# Interconnect_board_v1p7.net
KiCad netlist of a schematic drawn in EAGLE
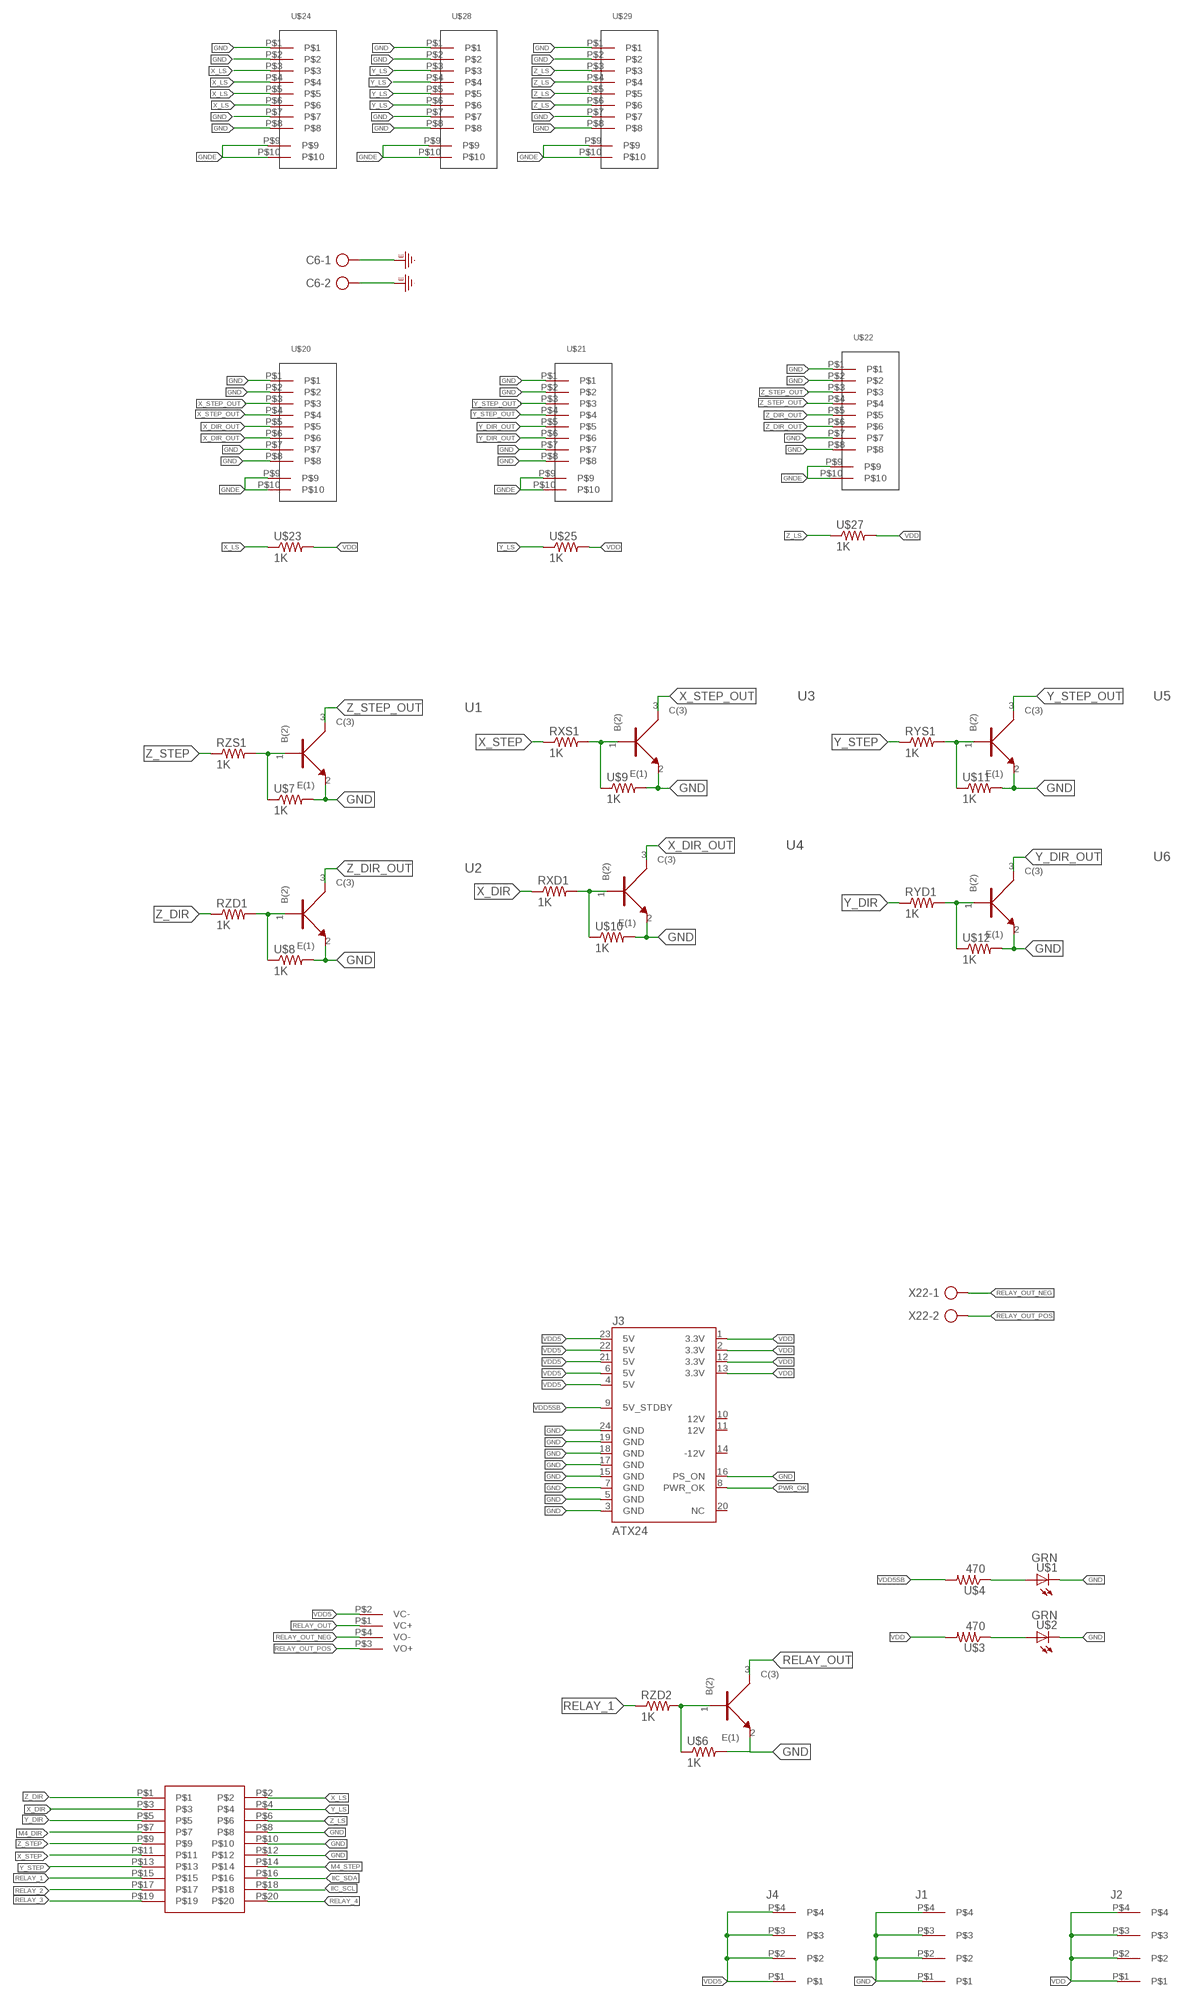
[diagram p0: schematic, sheet 1]

(export (version "E")
  (design (tool "Eeschema 10.0.6"))
  (components
    (comp (ref "C6")
      (value "AK300/2")
      (footprint "eagle-import:AK300_2")
      (libsource (lib "eagle-import") (part "AK300/2"))
    )
    (comp (ref "J1")
      (value "3.81MM_1_X_4_RT_ANGLE_PLUG_HEADER")
      (footprint "eagle-import:1X4_3.81MM_PITCH")
      (libsource (lib "eagle-import") (part "3.81MM_1_X_4_RT_ANGLE_PLUG_HEADER"))
    )
    (comp (ref "J2")
      (value "3.81MM_1_X_4_RT_ANGLE_PLUG_HEADER")
      (footprint "eagle-import:1X4_3.81MM_PITCH")
      (libsource (lib "eagle-import") (part "3.81MM_1_X_4_RT_ANGLE_PLUG_HEADER"))
    )
    (comp (ref "J3")
      (value "ATX24")
      (footprint "eagle-import:ATX24_STRAIGHT")
      (libsource (lib "eagle-import") (part "ATX24"))
    )
    (comp (ref "J4")
      (value "3.81MM_1_X_4_RT_ANGLE_PLUG_HEADER")
      (footprint "eagle-import:1X4_3.81MM_PITCH")
      (libsource (lib "eagle-import") (part "3.81MM_1_X_4_RT_ANGLE_PLUG_HEADER"))
    )
    (comp (ref "RXD1")
      (value "R_0805_1K")
      (footprint "eagle-import:R_0805_1K")
      (libsource (lib "eagle-import") (part "R_0805_1K"))
    )
    (comp (ref "RXS1")
      (value "R_0805_1K")
      (footprint "eagle-import:R_0805_1K")
      (libsource (lib "eagle-import") (part "R_0805_1K"))
    )
    (comp (ref "RYD1")
      (value "R_0805_1K")
      (footprint "eagle-import:R_0805_1K")
      (libsource (lib "eagle-import") (part "R_0805_1K"))
    )
    (comp (ref "RYS1")
      (value "R_0805_1K")
      (footprint "eagle-import:R_0805_1K")
      (libsource (lib "eagle-import") (part "R_0805_1K"))
    )
    (comp (ref "RZD1")
      (value "R_0805_1K")
      (footprint "eagle-import:R_0805_1K")
      (libsource (lib "eagle-import") (part "R_0805_1K"))
    )
    (comp (ref "RZD2")
      (value "R_0805_1K")
      (footprint "eagle-import:R_0805_1K")
      (libsource (lib "eagle-import") (part "R_0805_1K"))
    )
    (comp (ref "RZS1")
      (value "R_0805_1K")
      (footprint "eagle-import:R_0805_1K")
      (libsource (lib "eagle-import") (part "R_0805_1K"))
    )
    (comp (ref "U$1")
      (value "LED_0805_GREEN")
      (footprint "eagle-import:LED_0805_GREEN")
      (libsource (lib "eagle-import") (part "LED_0805_GREEN"))
    )
    (comp (ref "U$2")
      (value "LED_0805_GREEN")
      (footprint "eagle-import:LED_0805_GREEN")
      (libsource (lib "eagle-import") (part "LED_0805_GREEN"))
    )
    (comp (ref "U$3")
      (value "R_0805_470")
      (footprint "eagle-import:R_0805_470")
      (libsource (lib "eagle-import") (part "R_0805_470"))
    )
    (comp (ref "U$4")
      (value "R_0805_470")
      (footprint "eagle-import:R_0805_470")
      (libsource (lib "eagle-import") (part "R_0805_470"))
    )
    (comp (ref "U$5")
      (value "RELAY_KYOTO_KF0604D")
      (footprint "eagle-import:RELAY_KYOTO_KF0604D")
      (libsource (lib "eagle-import") (part "RELAY_KYOTO_KF0604D"))
    )
    (comp (ref "U$6")
      (value "R_0805_1K")
      (footprint "eagle-import:R_0805_1K")
      (libsource (lib "eagle-import") (part "R_0805_1K"))
    )
    (comp (ref "U$7")
      (value "R_0805_1K")
      (footprint "eagle-import:R_0805_1K")
      (libsource (lib "eagle-import") (part "R_0805_1K"))
    )
    (comp (ref "U$8")
      (value "R_0805_1K")
      (footprint "eagle-import:R_0805_1K")
      (libsource (lib "eagle-import") (part "R_0805_1K"))
    )
    (comp (ref "U$9")
      (value "R_0805_1K")
      (footprint "eagle-import:R_0805_1K")
      (libsource (lib "eagle-import") (part "R_0805_1K"))
    )
    (comp (ref "U$10")
      (value "R_0805_1K")
      (footprint "eagle-import:R_0805_1K")
      (libsource (lib "eagle-import") (part "R_0805_1K"))
    )
    (comp (ref "U$11")
      (value "R_0805_1K")
      (footprint "eagle-import:R_0805_1K")
      (libsource (lib "eagle-import") (part "R_0805_1K"))
    )
    (comp (ref "U$12")
      (value "R_0805_1K")
      (footprint "eagle-import:R_0805_1K")
      (libsource (lib "eagle-import") (part "R_0805_1K"))
    )
    (comp (ref "U$20")
      (value "RJ45_SMTRJ")
      (footprint "eagle-import:RJ45_SMT")
      (libsource (lib "eagle-import") (part "RJ45_SMTRJ"))
    )
    (comp (ref "U$21")
      (value "RJ45_SMTRJ")
      (footprint "eagle-import:RJ45_SMT")
      (libsource (lib "eagle-import") (part "RJ45_SMTRJ"))
    )
    (comp (ref "U$22")
      (value "RJ45_SMTRJ")
      (footprint "eagle-import:RJ45_SMT")
      (libsource (lib "eagle-import") (part "RJ45_SMTRJ"))
    )
    (comp (ref "U$23")
      (value "R_0805_1K")
      (footprint "eagle-import:R_0805_1K")
      (libsource (lib "eagle-import") (part "R_0805_1K"))
    )
    (comp (ref "U$24")
      (value "RJ45_SMTRJ")
      (footprint "eagle-import:RJ45_SMT")
      (libsource (lib "eagle-import") (part "RJ45_SMTRJ"))
    )
    (comp (ref "U$25")
      (value "R_0805_1K")
      (footprint "eagle-import:R_0805_1K")
      (libsource (lib "eagle-import") (part "R_0805_1K"))
    )
    (comp (ref "U$26")
      (value "2_X_10_HEADER_GENERIC")
      (footprint "eagle-import:2_X_10_.1_INCH")
      (libsource (lib "eagle-import") (part "2_X_10_HEADER_GENERIC"))
    )
    (comp (ref "U$27")
      (value "R_0805_1K")
      (footprint "eagle-import:R_0805_1K")
      (libsource (lib "eagle-import") (part "R_0805_1K"))
    )
    (comp (ref "U$28")
      (value "RJ45_SMTRJ")
      (footprint "eagle-import:RJ45_SMT")
      (libsource (lib "eagle-import") (part "RJ45_SMTRJ"))
    )
    (comp (ref "U$29")
      (value "RJ45_SMTRJ")
      (footprint "eagle-import:RJ45_SMT")
      (libsource (lib "eagle-import") (part "RJ45_SMTRJ"))
    )
    (comp (ref "U1")
      (value "BC846BW")
      (footprint "eagle-import:SOT323")
      (libsource (lib "eagle-import") (part "BC846BW"))
    )
    (comp (ref "U2")
      (value "BC846BW")
      (footprint "eagle-import:SOT323")
      (libsource (lib "eagle-import") (part "BC846BW"))
    )
    (comp (ref "U3")
      (value "BC846BW")
      (footprint "eagle-import:SOT323")
      (libsource (lib "eagle-import") (part "BC846BW"))
    )
    (comp (ref "U4")
      (value "BC846BW")
      (footprint "eagle-import:SOT323")
      (libsource (lib "eagle-import") (part "BC846BW"))
    )
    (comp (ref "U5")
      (value "BC846BW")
      (footprint "eagle-import:SOT323")
      (libsource (lib "eagle-import") (part "BC846BW"))
    )
    (comp (ref "U6")
      (value "BC846BW")
      (footprint "eagle-import:SOT323")
      (libsource (lib "eagle-import") (part "BC846BW"))
    )
    (comp (ref "U7")
      (value "BC846BW")
      (footprint "eagle-import:SOT323")
      (libsource (lib "eagle-import") (part "BC846BW"))
    )
    (comp (ref "X22")
      (value "AK300/2")
      (footprint "eagle-import:AK300_2")
      (libsource (lib "eagle-import") (part "AK300/2"))
    )
  )
  (nets
    (net (code "1") (name "GND") (class "Default")
      (node (ref "J1") (pin "P$1") (pinfunction "P$1_P$1") (pintype "bidirectional"))
      (node (ref "J1") (pin "P$2") (pinfunction "P$2_P$2") (pintype "bidirectional"))
      (node (ref "J1") (pin "P$3") (pinfunction "P$3_P$3") (pintype "bidirectional"))
      (node (ref "J1") (pin "P$4") (pinfunction "P$4_P$4") (pintype "bidirectional"))
      (node (ref "J3") (pin "15") (pinfunction "GND_15") (pintype "bidirectional"))
      (node (ref "J3") (pin "16") (pinfunction "PS_ON_16") (pintype "bidirectional"))
      (node (ref "J3") (pin "17") (pinfunction "GND_17") (pintype "bidirectional"))
      (node (ref "J3") (pin "18") (pinfunction "GND_18") (pintype "bidirectional"))
      (node (ref "J3") (pin "19") (pinfunction "GND_19") (pintype "bidirectional"))
      (node (ref "J3") (pin "24") (pinfunction "GND_24") (pintype "bidirectional"))
      (node (ref "J3") (pin "3") (pinfunction "GND_3") (pintype "bidirectional"))
      (node (ref "J3") (pin "5") (pinfunction "GND_5") (pintype "bidirectional"))
      (node (ref "J3") (pin "7") (pinfunction "GND_7") (pintype "bidirectional"))
      (node (ref "U$1") (pin "C") (pinfunction "C_C") (pintype "passive"))
      (node (ref "U$10") (pin "2") (pinfunction "2_2") (pintype "passive"))
      (node (ref "U$11") (pin "2") (pinfunction "2_2") (pintype "passive"))
      (node (ref "U$12") (pin "2") (pinfunction "2_2") (pintype "passive"))
      (node (ref "U$2") (pin "C") (pinfunction "C_C") (pintype "passive"))
      (node (ref "U$20") (pin "P$1") (pinfunction "P$1_P$1") (pintype "bidirectional"))
      (node (ref "U$20") (pin "P$2") (pinfunction "P$2_P$2") (pintype "bidirectional"))
      (node (ref "U$20") (pin "P$7") (pinfunction "P$7_P$7") (pintype "bidirectional"))
      (node (ref "U$20") (pin "P$8") (pinfunction "P$8_P$8") (pintype "bidirectional"))
      (node (ref "U$21") (pin "P$1") (pinfunction "P$1_P$1") (pintype "bidirectional"))
      (node (ref "U$21") (pin "P$2") (pinfunction "P$2_P$2") (pintype "bidirectional"))
      (node (ref "U$21") (pin "P$7") (pinfunction "P$7_P$7") (pintype "bidirectional"))
      (node (ref "U$21") (pin "P$8") (pinfunction "P$8_P$8") (pintype "bidirectional"))
      (node (ref "U$22") (pin "P$1") (pinfunction "P$1_P$1") (pintype "bidirectional"))
      (node (ref "U$22") (pin "P$2") (pinfunction "P$2_P$2") (pintype "bidirectional"))
      (node (ref "U$22") (pin "P$7") (pinfunction "P$7_P$7") (pintype "bidirectional"))
      (node (ref "U$22") (pin "P$8") (pinfunction "P$8_P$8") (pintype "bidirectional"))
      (node (ref "U$24") (pin "P$1") (pinfunction "P$1_P$1") (pintype "bidirectional"))
      (node (ref "U$24") (pin "P$2") (pinfunction "P$2_P$2") (pintype "bidirectional"))
      (node (ref "U$24") (pin "P$7") (pinfunction "P$7_P$7") (pintype "bidirectional"))
      (node (ref "U$24") (pin "P$8") (pinfunction "P$8_P$8") (pintype "bidirectional"))
      (node (ref "U$26") (pin "P$10") (pinfunction "P$10_P$10") (pintype "bidirectional"))
      (node (ref "U$26") (pin "P$12") (pinfunction "P$12_P$12") (pintype "bidirectional"))
      (node (ref "U$26") (pin "P$8") (pinfunction "P$8_P$8") (pintype "bidirectional"))
      (node (ref "U$28") (pin "P$1") (pinfunction "P$1_P$1") (pintype "bidirectional"))
      (node (ref "U$28") (pin "P$2") (pinfunction "P$2_P$2") (pintype "bidirectional"))
      (node (ref "U$28") (pin "P$7") (pinfunction "P$7_P$7") (pintype "bidirectional"))
      (node (ref "U$28") (pin "P$8") (pinfunction "P$8_P$8") (pintype "bidirectional"))
      (node (ref "U$29") (pin "P$1") (pinfunction "P$1_P$1") (pintype "bidirectional"))
      (node (ref "U$29") (pin "P$2") (pinfunction "P$2_P$2") (pintype "bidirectional"))
      (node (ref "U$29") (pin "P$7") (pinfunction "P$7_P$7") (pintype "bidirectional"))
      (node (ref "U$29") (pin "P$8") (pinfunction "P$8_P$8") (pintype "bidirectional"))
      (node (ref "U$6") (pin "2") (pinfunction "2_2") (pintype "passive"))
      (node (ref "U$7") (pin "2") (pinfunction "2_2") (pintype "passive"))
      (node (ref "U$8") (pin "2") (pinfunction "2_2") (pintype "passive"))
      (node (ref "U$9") (pin "2") (pinfunction "2_2") (pintype "passive"))
      (node (ref "U1") (pin "2") (pinfunction "E(1)_2") (pintype "output"))
      (node (ref "U2") (pin "2") (pinfunction "E(1)_2") (pintype "output"))
      (node (ref "U3") (pin "2") (pinfunction "E(1)_2") (pintype "output"))
      (node (ref "U4") (pin "2") (pinfunction "E(1)_2") (pintype "output"))
      (node (ref "U5") (pin "2") (pinfunction "E(1)_2") (pintype "output"))
      (node (ref "U6") (pin "2") (pinfunction "E(1)_2") (pintype "output"))
      (node (ref "U7") (pin "2") (pinfunction "E(1)_2") (pintype "output"))
    )
    (net (code "2") (name "GNDE") (class "Default")
      (node (ref "C6") (pin "1") (pinfunction "KL_1") (pintype "passive"))
      (node (ref "C6") (pin "2") (pinfunction "KL_2") (pintype "passive"))
      (node (ref "U$20") (pin "P$10") (pinfunction "P$10_P$10") (pintype "bidirectional"))
      (node (ref "U$20") (pin "P$9") (pinfunction "P$9_P$9") (pintype "bidirectional"))
      (node (ref "U$21") (pin "P$10") (pinfunction "P$10_P$10") (pintype "bidirectional"))
      (node (ref "U$21") (pin "P$9") (pinfunction "P$9_P$9") (pintype "bidirectional"))
      (node (ref "U$22") (pin "P$10") (pinfunction "P$10_P$10") (pintype "bidirectional"))
      (node (ref "U$22") (pin "P$9") (pinfunction "P$9_P$9") (pintype "bidirectional"))
      (node (ref "U$24") (pin "P$10") (pinfunction "P$10_P$10") (pintype "bidirectional"))
      (node (ref "U$24") (pin "P$9") (pinfunction "P$9_P$9") (pintype "bidirectional"))
      (node (ref "U$28") (pin "P$10") (pinfunction "P$10_P$10") (pintype "bidirectional"))
      (node (ref "U$28") (pin "P$9") (pinfunction "P$9_P$9") (pintype "bidirectional"))
      (node (ref "U$29") (pin "P$10") (pinfunction "P$10_P$10") (pintype "bidirectional"))
      (node (ref "U$29") (pin "P$9") (pinfunction "P$9_P$9") (pintype "bidirectional"))
    )
    (net (code "3") (name "IIC_SCL") (class "Default")
      (node (ref "U$26") (pin "P$18") (pinfunction "P$18_P$18") (pintype "bidirectional"))
    )
    (net (code "4") (name "IIC_SDA") (class "Default")
      (node (ref "U$26") (pin "P$16") (pinfunction "P$16_P$16") (pintype "bidirectional"))
    )
    (net (code "5") (name "M4_DIR") (class "Default")
      (node (ref "U$26") (pin "P$7") (pinfunction "P$7_P$7") (pintype "bidirectional"))
    )
    (net (code "6") (name "M4_STEP") (class "Default")
      (node (ref "U$26") (pin "P$14") (pinfunction "P$14_P$14") (pintype "bidirectional"))
    )
    (net (code "7") (name "Net-(U$1-PadA)") (class "Default")
      (node (ref "U$1") (pin "A") (pinfunction "A_A") (pintype "passive"))
      (node (ref "U$4") (pin "1") (pinfunction "1_1") (pintype "passive"))
    )
    (net (code "8") (name "Net-(U$2-PadA)") (class "Default")
      (node (ref "U$2") (pin "A") (pinfunction "A_A") (pintype "passive"))
      (node (ref "U$3") (pin "1") (pinfunction "1_1") (pintype "passive"))
    )
    (net (code "9") (name "Net-(U1-B(2))") (class "Default")
      (node (ref "RZS1") (pin "2") (pinfunction "2_2") (pintype "passive"))
      (node (ref "U$7") (pin "1") (pinfunction "1_1") (pintype "passive"))
      (node (ref "U1") (pin "1") (pinfunction "B(2)_1") (pintype "input"))
    )
    (net (code "10") (name "Net-(U2-B(2))") (class "Default")
      (node (ref "RZD1") (pin "2") (pinfunction "2_2") (pintype "passive"))
      (node (ref "U$8") (pin "1") (pinfunction "1_1") (pintype "passive"))
      (node (ref "U2") (pin "1") (pinfunction "B(2)_1") (pintype "input"))
    )
    (net (code "11") (name "Net-(U3-B(2))") (class "Default")
      (node (ref "RXS1") (pin "2") (pinfunction "2_2") (pintype "passive"))
      (node (ref "U$9") (pin "1") (pinfunction "1_1") (pintype "passive"))
      (node (ref "U3") (pin "1") (pinfunction "B(2)_1") (pintype "input"))
    )
    (net (code "12") (name "Net-(U4-B(2))") (class "Default")
      (node (ref "RXD1") (pin "2") (pinfunction "2_2") (pintype "passive"))
      (node (ref "U$10") (pin "1") (pinfunction "1_1") (pintype "passive"))
      (node (ref "U4") (pin "1") (pinfunction "B(2)_1") (pintype "input"))
    )
    (net (code "13") (name "Net-(U5-B(2))") (class "Default")
      (node (ref "RYS1") (pin "2") (pinfunction "2_2") (pintype "passive"))
      (node (ref "U$11") (pin "1") (pinfunction "1_1") (pintype "passive"))
      (node (ref "U5") (pin "1") (pinfunction "B(2)_1") (pintype "input"))
    )
    (net (code "14") (name "Net-(U6-B(2))") (class "Default")
      (node (ref "RYD1") (pin "2") (pinfunction "2_2") (pintype "passive"))
      (node (ref "U$12") (pin "1") (pinfunction "1_1") (pintype "passive"))
      (node (ref "U6") (pin "1") (pinfunction "B(2)_1") (pintype "input"))
    )
    (net (code "15") (name "Net-(U7-B(2))") (class "Default")
      (node (ref "RZD2") (pin "2") (pinfunction "2_2") (pintype "passive"))
      (node (ref "U$6") (pin "1") (pinfunction "1_1") (pintype "passive"))
      (node (ref "U7") (pin "1") (pinfunction "B(2)_1") (pintype "input"))
    )
    (net (code "16") (name "PWR_OK") (class "Default")
      (node (ref "J3") (pin "8") (pinfunction "PWR_OK_8") (pintype "bidirectional"))
    )
    (net (code "17") (name "RELAY_1") (class "Default")
      (node (ref "RZD2") (pin "1") (pinfunction "1_1") (pintype "passive"))
      (node (ref "U$26") (pin "P$15") (pinfunction "P$15_P$15") (pintype "bidirectional"))
    )
    (net (code "18") (name "RELAY_2") (class "Default")
      (node (ref "U$26") (pin "P$17") (pinfunction "P$17_P$17") (pintype "bidirectional"))
    )
    (net (code "19") (name "RELAY_3") (class "Default")
      (node (ref "U$26") (pin "P$19") (pinfunction "P$19_P$19") (pintype "bidirectional"))
    )
    (net (code "20") (name "RELAY_4") (class "Default")
      (node (ref "U$26") (pin "P$20") (pinfunction "P$20_P$20") (pintype "bidirectional"))
    )
    (net (code "21") (name "RELAY_OUT") (class "Default")
      (node (ref "U$5") (pin "P$1") (pinfunction "VC+_P$1") (pintype "bidirectional"))
      (node (ref "U7") (pin "3") (pinfunction "C(3)_3") (pintype "input"))
    )
    (net (code "22") (name "RELAY_OUT_NEG") (class "Default")
      (node (ref "U$5") (pin "P$4") (pinfunction "VO-_P$4") (pintype "bidirectional"))
      (node (ref "X22") (pin "1") (pinfunction "KL_1") (pintype "passive"))
    )
    (net (code "23") (name "RELAY_OUT_POS") (class "Default")
      (node (ref "U$5") (pin "P$3") (pinfunction "VO+_P$3") (pintype "bidirectional"))
      (node (ref "X22") (pin "2") (pinfunction "KL_2") (pintype "passive"))
    )
    (net (code "24") (name "VDD") (class "Default")
      (node (ref "J2") (pin "P$1") (pinfunction "P$1_P$1") (pintype "bidirectional"))
      (node (ref "J2") (pin "P$2") (pinfunction "P$2_P$2") (pintype "bidirectional"))
      (node (ref "J2") (pin "P$3") (pinfunction "P$3_P$3") (pintype "bidirectional"))
      (node (ref "J2") (pin "P$4") (pinfunction "P$4_P$4") (pintype "bidirectional"))
      (node (ref "J3") (pin "1") (pinfunction "3.3V_1") (pintype "bidirectional"))
      (node (ref "J3") (pin "12") (pinfunction "3.3V_12") (pintype "bidirectional"))
      (node (ref "J3") (pin "13") (pinfunction "3.3V_13") (pintype "bidirectional"))
      (node (ref "J3") (pin "2") (pinfunction "3.3V_2") (pintype "bidirectional"))
      (node (ref "U$23") (pin "2") (pinfunction "2_2") (pintype "passive"))
      (node (ref "U$25") (pin "2") (pinfunction "2_2") (pintype "passive"))
      (node (ref "U$27") (pin "2") (pinfunction "2_2") (pintype "passive"))
      (node (ref "U$3") (pin "2") (pinfunction "2_2") (pintype "passive"))
    )
    (net (code "25") (name "VDD5") (class "Default")
      (node (ref "J3") (pin "21") (pinfunction "5V_21") (pintype "bidirectional"))
      (node (ref "J3") (pin "22") (pinfunction "5V_22") (pintype "bidirectional"))
      (node (ref "J3") (pin "23") (pinfunction "5V_23") (pintype "bidirectional"))
      (node (ref "J3") (pin "4") (pinfunction "5V_4") (pintype "bidirectional"))
      (node (ref "J3") (pin "6") (pinfunction "5V_6") (pintype "bidirectional"))
      (node (ref "J4") (pin "P$1") (pinfunction "P$1_P$1") (pintype "bidirectional"))
      (node (ref "J4") (pin "P$2") (pinfunction "P$2_P$2") (pintype "bidirectional"))
      (node (ref "J4") (pin "P$3") (pinfunction "P$3_P$3") (pintype "bidirectional"))
      (node (ref "J4") (pin "P$4") (pinfunction "P$4_P$4") (pintype "bidirectional"))
      (node (ref "U$5") (pin "P$2") (pinfunction "VC-_P$2") (pintype "bidirectional"))
    )
    (net (code "26") (name "VDD5SB") (class "Default")
      (node (ref "J3") (pin "9") (pinfunction "5V_STDBY_9") (pintype "bidirectional"))
      (node (ref "U$4") (pin "2") (pinfunction "2_2") (pintype "passive"))
    )
    (net (code "27") (name "X_DIR") (class "Default")
      (node (ref "RXD1") (pin "1") (pinfunction "1_1") (pintype "passive"))
      (node (ref "U$26") (pin "P$3") (pinfunction "P$3_P$3") (pintype "bidirectional"))
    )
    (net (code "28") (name "X_DIR_OUT") (class "Default")
      (node (ref "U$20") (pin "P$5") (pinfunction "P$5_P$5") (pintype "bidirectional"))
      (node (ref "U$20") (pin "P$6") (pinfunction "P$6_P$6") (pintype "bidirectional"))
      (node (ref "U4") (pin "3") (pinfunction "C(3)_3") (pintype "input"))
    )
    (net (code "29") (name "X_LS") (class "Default")
      (node (ref "U$23") (pin "1") (pinfunction "1_1") (pintype "passive"))
      (node (ref "U$24") (pin "P$3") (pinfunction "P$3_P$3") (pintype "bidirectional"))
      (node (ref "U$24") (pin "P$4") (pinfunction "P$4_P$4") (pintype "bidirectional"))
      (node (ref "U$24") (pin "P$5") (pinfunction "P$5_P$5") (pintype "bidirectional"))
      (node (ref "U$24") (pin "P$6") (pinfunction "P$6_P$6") (pintype "bidirectional"))
      (node (ref "U$26") (pin "P$2") (pinfunction "P$2_P$2") (pintype "bidirectional"))
    )
    (net (code "30") (name "X_STEP") (class "Default")
      (node (ref "RXS1") (pin "1") (pinfunction "1_1") (pintype "passive"))
      (node (ref "U$26") (pin "P$11") (pinfunction "P$11_P$11") (pintype "bidirectional"))
    )
    (net (code "31") (name "X_STEP_OUT") (class "Default")
      (node (ref "U$20") (pin "P$3") (pinfunction "P$3_P$3") (pintype "bidirectional"))
      (node (ref "U$20") (pin "P$4") (pinfunction "P$4_P$4") (pintype "bidirectional"))
      (node (ref "U3") (pin "3") (pinfunction "C(3)_3") (pintype "input"))
    )
    (net (code "32") (name "Y_DIR") (class "Default")
      (node (ref "RYD1") (pin "1") (pinfunction "1_1") (pintype "passive"))
      (node (ref "U$26") (pin "P$5") (pinfunction "P$5_P$5") (pintype "bidirectional"))
    )
    (net (code "33") (name "Y_DIR_OUT") (class "Default")
      (node (ref "U$21") (pin "P$5") (pinfunction "P$5_P$5") (pintype "bidirectional"))
      (node (ref "U$21") (pin "P$6") (pinfunction "P$6_P$6") (pintype "bidirectional"))
      (node (ref "U6") (pin "3") (pinfunction "C(3)_3") (pintype "input"))
    )
    (net (code "34") (name "Y_LS") (class "Default")
      (node (ref "U$25") (pin "1") (pinfunction "1_1") (pintype "passive"))
      (node (ref "U$26") (pin "P$4") (pinfunction "P$4_P$4") (pintype "bidirectional"))
      (node (ref "U$28") (pin "P$3") (pinfunction "P$3_P$3") (pintype "bidirectional"))
      (node (ref "U$28") (pin "P$4") (pinfunction "P$4_P$4") (pintype "bidirectional"))
      (node (ref "U$28") (pin "P$5") (pinfunction "P$5_P$5") (pintype "bidirectional"))
      (node (ref "U$28") (pin "P$6") (pinfunction "P$6_P$6") (pintype "bidirectional"))
    )
    (net (code "35") (name "Y_STEP") (class "Default")
      (node (ref "RYS1") (pin "1") (pinfunction "1_1") (pintype "passive"))
      (node (ref "U$26") (pin "P$13") (pinfunction "P$13_P$13") (pintype "bidirectional"))
    )
    (net (code "36") (name "Y_STEP_OUT") (class "Default")
      (node (ref "U$21") (pin "P$3") (pinfunction "P$3_P$3") (pintype "bidirectional"))
      (node (ref "U$21") (pin "P$4") (pinfunction "P$4_P$4") (pintype "bidirectional"))
      (node (ref "U5") (pin "3") (pinfunction "C(3)_3") (pintype "input"))
    )
    (net (code "37") (name "Z_DIR") (class "Default")
      (node (ref "RZD1") (pin "1") (pinfunction "1_1") (pintype "passive"))
      (node (ref "U$26") (pin "P$1") (pinfunction "P$1_P$1") (pintype "bidirectional"))
    )
    (net (code "38") (name "Z_DIR_OUT") (class "Default")
      (node (ref "U$22") (pin "P$5") (pinfunction "P$5_P$5") (pintype "bidirectional"))
      (node (ref "U$22") (pin "P$6") (pinfunction "P$6_P$6") (pintype "bidirectional"))
      (node (ref "U2") (pin "3") (pinfunction "C(3)_3") (pintype "input"))
    )
    (net (code "39") (name "Z_LS") (class "Default")
      (node (ref "U$26") (pin "P$6") (pinfunction "P$6_P$6") (pintype "bidirectional"))
      (node (ref "U$27") (pin "1") (pinfunction "1_1") (pintype "passive"))
      (node (ref "U$29") (pin "P$3") (pinfunction "P$3_P$3") (pintype "bidirectional"))
      (node (ref "U$29") (pin "P$4") (pinfunction "P$4_P$4") (pintype "bidirectional"))
      (node (ref "U$29") (pin "P$5") (pinfunction "P$5_P$5") (pintype "bidirectional"))
      (node (ref "U$29") (pin "P$6") (pinfunction "P$6_P$6") (pintype "bidirectional"))
    )
    (net (code "40") (name "Z_STEP") (class "Default")
      (node (ref "RZS1") (pin "1") (pinfunction "1_1") (pintype "passive"))
      (node (ref "U$26") (pin "P$9") (pinfunction "P$9_P$9") (pintype "bidirectional"))
    )
    (net (code "41") (name "Z_STEP_OUT") (class "Default")
      (node (ref "U$22") (pin "P$3") (pinfunction "P$3_P$3") (pintype "bidirectional"))
      (node (ref "U$22") (pin "P$4") (pinfunction "P$4_P$4") (pintype "bidirectional"))
      (node (ref "U1") (pin "3") (pinfunction "C(3)_3") (pintype "input"))
    )
    (net (code "42") (name "unconnected-(J3--12V-Pad14)") (class "Default")
      (node (ref "J3") (pin "14") (pinfunction "-12V_14") (pintype "bidirectional"))
    )
    (net (code "43") (name "unconnected-(J3-12V-Pad10)") (class "Default")
      (node (ref "J3") (pin "10") (pinfunction "12V_10") (pintype "bidirectional"))
    )
    (net (code "44") (name "unconnected-(J3-12V-Pad11)") (class "Default")
      (node (ref "J3") (pin "11") (pinfunction "12V_11") (pintype "bidirectional"))
    )
    (net (code "45") (name "unconnected-(J3-NC-Pad20)") (class "Default")
      (node (ref "J3") (pin "20") (pinfunction "NC_20") (pintype "bidirectional"))
    )
  )
)
